# Metro_Mini_Rev_B.net
KiCad netlist of a schematic drawn in EAGLE
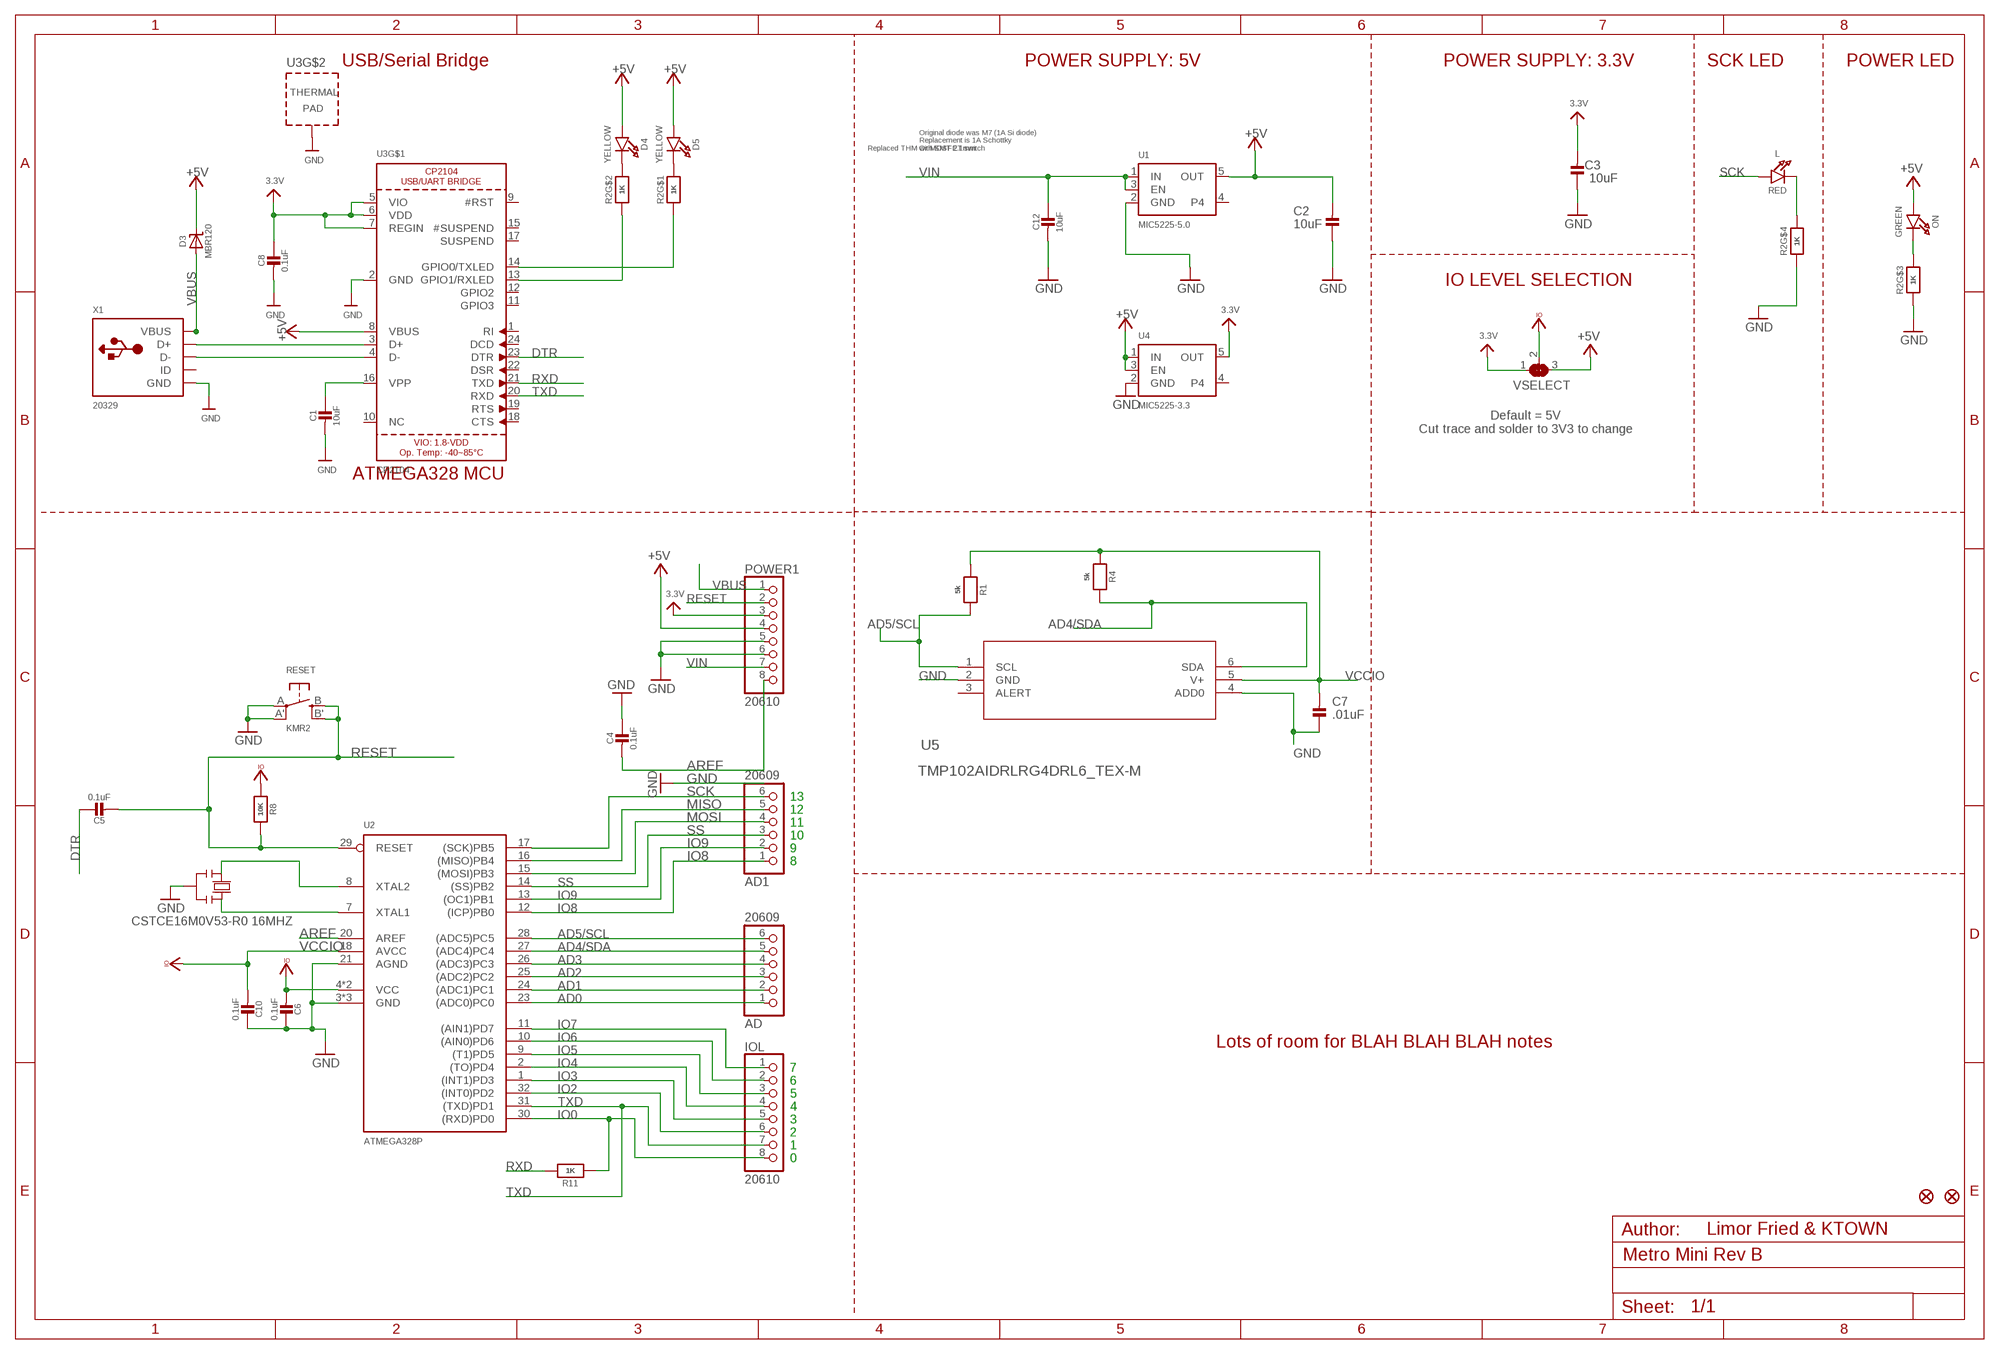
[diagram p0: schematic, sheet 1]

(export (version "E")
  (design (tool "Eeschema 10.0.6"))
  (components
    (comp (ref "AD")
      (value "20609")
      (footprint "eagle-import:1X06_ROUND")
      (libsource (lib "eagle-import") (part "HEADER-1X6ROUND"))
    )
    (comp (ref "AD1")
      (value "20609")
      (footprint "eagle-import:1X06_ROUND")
      (libsource (lib "eagle-import") (part "HEADER-1X6ROUND"))
    )
    (comp (ref "C1")
      (value "10uF")
      (footprint "eagle-import:0805-NO")
      (libsource (lib "eagle-import") (part "CAP_CERAMIC0805-NOOUTLINE"))
    )
    (comp (ref "C2")
      (value "10uF")
      (footprint "eagle-import:0805-NO")
      (libsource (lib "eagle-import") (part "CAP_CERAMIC0805-NOOUTLINE"))
    )
    (comp (ref "C3")
      (value "10uF")
      (footprint "eagle-import:0805-NO")
      (libsource (lib "eagle-import") (part "CAP_CERAMIC0805-NOOUTLINE"))
    )
    (comp (ref "C4")
      (value "0.1uF")
      (footprint "eagle-import:0805-NO")
      (libsource (lib "eagle-import") (part "CAP_CERAMIC0805-NOOUTLINE"))
    )
    (comp (ref "C5")
      (value "0.1uF")
      (footprint "eagle-import:_0805MP")
      (libsource (lib "eagle-import") (part "CAP_CERAMIC_0805MP"))
    )
    (comp (ref "C6")
      (value "0.1uF")
      (footprint "eagle-import:0805-NO")
      (libsource (lib "eagle-import") (part "CAP_CERAMIC0805-NOOUTLINE"))
    )
    (comp (ref "C7")
      (value ".01uF")
      (footprint "eagle-import:0805-NO")
      (libsource (lib "eagle-import") (part "CAP_CERAMIC0805-NOOUTLINE"))
    )
    (comp (ref "C8")
      (value "0.1uF")
      (footprint "eagle-import:0805-NO")
      (libsource (lib "eagle-import") (part "CAP_CERAMIC0805-NOOUTLINE"))
    )
    (comp (ref "C10")
      (value "0.1uF")
      (footprint "eagle-import:0805-NO")
      (libsource (lib "eagle-import") (part "CAP_CERAMIC0805-NOOUTLINE"))
    )
    (comp (ref "C12")
      (value "10uF")
      (footprint "eagle-import:0805-NO")
      (libsource (lib "eagle-import") (part "CAP_CERAMIC0805-NOOUTLINE"))
    )
    (comp (ref "D3")
      (value "MBR120")
      (footprint "eagle-import:SOD-123")
      (libsource (lib "eagle-import") (part "DIODE-SCHOTTKYSOD-123"))
    )
    (comp (ref "D4")
      (value "YELLOW")
      (footprint "eagle-import:CHIPLED_0805_NOOUTLINE")
      (libsource (lib "eagle-import") (part "LED0805_NOOUTLINE"))
    )
    (comp (ref "D5")
      (value "YELLOW")
      (footprint "eagle-import:CHIPLED_0805_NOOUTLINE")
      (libsource (lib "eagle-import") (part "LED0805_NOOUTLINE"))
    )
    (comp (ref "FD1")
      (value "FIDUCIAL\"\"")
      (footprint "eagle-import:FIDUCIAL_1MM")
      (libsource (lib "eagle-import") (part "FIDUCIAL{dblquote}{dblquote}"))
    )
    (comp (ref "FD2")
      (value "FIDUCIAL\"\"")
      (footprint "eagle-import:FIDUCIAL_1MM")
      (libsource (lib "eagle-import") (part "FIDUCIAL{dblquote}{dblquote}"))
    )
    (comp (ref "IOL")
      (value "20610")
      (footprint "eagle-import:1X08_ROUND")
      (libsource (lib "eagle-import") (part "HEADER-1X8ROUND"))
    )
    (comp (ref "L")
      (value "RED")
      (footprint "eagle-import:CHIPLED_0805_NOOUTLINE")
      (libsource (lib "eagle-import") (part "LED0805_NOOUTLINE"))
    )
    (comp (ref "ON")
      (value "GREEN")
      (footprint "eagle-import:CHIPLED_0805_NOOUTLINE")
      (libsource (lib "eagle-import") (part "LED0805_NOOUTLINE"))
    )
    (comp (ref "POWER1")
      (value "20610")
      (footprint "eagle-import:1X08_ROUND_70")
      (libsource (lib "eagle-import") (part "HEADER-1X870MIL"))
    )
    (comp (ref "R1")
      (value "5k")
      (footprint "eagle-import:0805-NO")
      (libsource (lib "eagle-import") (part "RESISTOR0805_NOOUTLINE"))
    )
    (comp (ref "R2")
      (value "1K")
      (footprint "eagle-import:RESPACK_4X0603")
      (libsource (lib "eagle-import") (part "RESISTOR_4PACK"))
    )
    (comp (ref "R4")
      (value "5k")
      (footprint "eagle-import:0805-NO")
      (libsource (lib "eagle-import") (part "RESISTOR0805_NOOUTLINE"))
    )
    (comp (ref "R8")
      (value "10K")
      (footprint "eagle-import:0805-NO")
      (libsource (lib "eagle-import") (part "RESISTOR0805_NOOUTLINE"))
    )
    (comp (ref "R11")
      (value "1K")
      (footprint "eagle-import:0805-NO")
      (libsource (lib "eagle-import") (part "RESISTOR0805_NOOUTLINE"))
    )
    (comp (ref "RESET")
      (value "KMR2")
      (footprint "eagle-import:BTN_KMR2_4.6X2.8")
      (libsource (lib "eagle-import") (part "SWITCH_TACT_SMT4.6X2.8"))
    )
    (comp (ref "U1")
      (value "MIC5225-5.0")
      (footprint "eagle-import:SOT23-5")
      (libsource (lib "eagle-import") (part "VREG_SOT23-5"))
    )
    (comp (ref "U2")
      (value "ATMEGA328P")
      (footprint "eagle-import:MLF32-TH")
      (libsource (lib "eagle-import") (part "ATMEGA328P"))
    )
    (comp (ref "U3")
      (value "CP2104")
      (footprint "eagle-import:QFN24_4MM_SMSC")
      (libsource (lib "eagle-import") (part "CP2104"))
    )
    (comp (ref "U4")
      (value "MIC5225-3.3")
      (footprint "eagle-import:SOT23-5")
      (libsource (lib "eagle-import") (part "VREG_SOT23-5"))
    )
    (comp (ref "U5")
      (value "TMP102AIDRLRG4DRL6_TEX-M")
      (footprint "eagle-import:DRL6_TEX-M")
      (fields
        (field (name "MANUFACTURER") "Texas Instruments")
        (field (name "MANUFACTURER_PART_NUMBER") "TMP102AIDRLRG4")
        (field (name "COPYRIGHT") "Copyright (C) 2018 Accelerated Designs. All rights reserved")
      )
      (libsource (lib "eagle-import") (part "TMP102AIDRLRG4DRL6_TEX-M"))
    )
    (comp (ref "VSELECT")
      (value "SOLDERJUMPER_2WAY")
      (footprint "eagle-import:SOLDERJUMPER_2WAY_OPEN_NOPASTE")
      (libsource (lib "eagle-import") (part "SOLDERJUMPER_2WAY"))
    )
    (comp (ref "X1")
      (value "20329")
      (footprint "eagle-import:4UCONN_20329_V2")
      (libsource (lib "eagle-import") (part "USB_MICRO_20329_V2"))
    )
    (comp (ref "Y2")
      (value "CSTCE16M0V53-R0 16MHZ")
      (footprint "eagle-import:RESONATOR")
      (libsource (lib "eagle-import") (part "RESONATORMU"))
    )
  )
  (nets
    (net (code "1") (name "+5V") (class "Default")
      (node (ref "C2") (pin "2") (pinfunction "2_2") (pintype "passive"))
      (node (ref "D3") (pin "C") (pinfunction "C_C") (pintype "passive"))
      (node (ref "D4") (pin "A") (pinfunction "A_A") (pintype "passive"))
      (node (ref "D5") (pin "A") (pinfunction "A_A") (pintype "passive"))
      (node (ref "ON") (pin "A") (pinfunction "A_A") (pintype "passive"))
      (node (ref "POWER1") (pin "4") (pinfunction "4_4") (pintype "passive"))
      (node (ref "U1") (pin "5") (pinfunction "OUT_5") (pintype "power_in"))
      (node (ref "U3") (pin "8") (pinfunction "VBUS_8") (pintype "power_in"))
      (node (ref "U4") (pin "1") (pinfunction "IN_1") (pintype "power_in"))
      (node (ref "U4") (pin "3") (pinfunction "EN_3") (pintype "input"))
      (node (ref "VSELECT") (pin "3") (pinfunction "3_3") (pintype "passive"))
    )
    (net (code "2") (name "/AD0") (class "Default")
      (node (ref "AD") (pin "1") (pinfunction "1_1") (pintype "passive"))
      (node (ref "U2") (pin "23") (pinfunction "(ADC0)PC0_23") (pintype "bidirectional"))
    )
    (net (code "3") (name "/AD1") (class "Default")
      (node (ref "AD") (pin "2") (pinfunction "2_2") (pintype "passive"))
      (node (ref "U2") (pin "24") (pinfunction "(ADC1)PC1_24") (pintype "bidirectional"))
    )
    (net (code "4") (name "/AD2") (class "Default")
      (node (ref "AD") (pin "3") (pinfunction "3_3") (pintype "passive"))
      (node (ref "U2") (pin "25") (pinfunction "(ADC2)PC2_25") (pintype "bidirectional"))
    )
    (net (code "5") (name "/AD3") (class "Default")
      (node (ref "AD") (pin "4") (pinfunction "4_4") (pintype "passive"))
      (node (ref "U2") (pin "26") (pinfunction "(ADC3)PC3_26") (pintype "bidirectional"))
    )
    (net (code "6") (name "/AD4{slash}SDA") (class "Default")
      (node (ref "AD") (pin "5") (pinfunction "5_5") (pintype "passive"))
      (node (ref "R4") (pin "2") (pinfunction "2_2") (pintype "passive"))
      (node (ref "U2") (pin "27") (pinfunction "(ADC4)PC4_27") (pintype "bidirectional"))
      (node (ref "U5") (pin "6") (pinfunction "SDA_6") (pintype "passive"))
    )
    (net (code "7") (name "/AD5{slash}SCL") (class "Default")
      (node (ref "AD") (pin "6") (pinfunction "6_6") (pintype "passive"))
      (node (ref "R1") (pin "2") (pinfunction "2_2") (pintype "passive"))
      (node (ref "U2") (pin "28") (pinfunction "(ADC5)PC5_28") (pintype "bidirectional"))
      (node (ref "U5") (pin "1") (pinfunction "SCL_1") (pintype "passive"))
    )
    (net (code "8") (name "/AREF") (class "Default")
      (node (ref "C4") (pin "2") (pinfunction "2_2") (pintype "passive"))
      (node (ref "POWER1") (pin "8") (pinfunction "8_8") (pintype "passive"))
      (node (ref "U2") (pin "20") (pinfunction "AREF_20") (pintype "power_in"))
    )
    (net (code "9") (name "/DTR") (class "Default")
      (node (ref "C5") (pin "1") (pinfunction "1_1") (pintype "passive"))
      (node (ref "U3") (pin "23") (pinfunction "DTR_23") (pintype "output"))
    )
    (net (code "10") (name "/IO0") (class "Default")
      (node (ref "IOL") (pin "8") (pinfunction "8_8") (pintype "passive"))
      (node (ref "R11") (pin "1") (pinfunction "1_1") (pintype "passive"))
      (node (ref "U2") (pin "30") (pinfunction "(RXD)PD0_30") (pintype "bidirectional"))
    )
    (net (code "11") (name "/IO2") (class "Default")
      (node (ref "IOL") (pin "6") (pinfunction "6_6") (pintype "passive"))
      (node (ref "U2") (pin "32") (pinfunction "(INT0)PD2_32") (pintype "bidirectional"))
    )
    (net (code "12") (name "/IO3") (class "Default")
      (node (ref "IOL") (pin "5") (pinfunction "5_5") (pintype "passive"))
      (node (ref "U2") (pin "1") (pinfunction "(INT1)PD3_1") (pintype "bidirectional"))
    )
    (net (code "13") (name "/IO4") (class "Default")
      (node (ref "IOL") (pin "4") (pinfunction "4_4") (pintype "passive"))
      (node (ref "U2") (pin "2") (pinfunction "(TO)PD4_2") (pintype "bidirectional"))
    )
    (net (code "14") (name "/IO5") (class "Default")
      (node (ref "IOL") (pin "3") (pinfunction "3_3") (pintype "passive"))
      (node (ref "U2") (pin "9") (pinfunction "(T1)PD5_9") (pintype "bidirectional"))
    )
    (net (code "15") (name "/IO6") (class "Default")
      (node (ref "IOL") (pin "2") (pinfunction "2_2") (pintype "passive"))
      (node (ref "U2") (pin "10") (pinfunction "(AIN0)PD6_10") (pintype "bidirectional"))
    )
    (net (code "16") (name "/IO7") (class "Default")
      (node (ref "IOL") (pin "1") (pinfunction "1_1") (pintype "passive"))
      (node (ref "U2") (pin "11") (pinfunction "(AIN1)PD7_11") (pintype "bidirectional"))
    )
    (net (code "17") (name "/IO8") (class "Default")
      (node (ref "AD1") (pin "1") (pinfunction "1_1") (pintype "passive"))
      (node (ref "U2") (pin "12") (pinfunction "(ICP)PB0_12") (pintype "bidirectional"))
    )
    (net (code "18") (name "/IO9") (class "Default")
      (node (ref "AD1") (pin "2") (pinfunction "2_2") (pintype "passive"))
      (node (ref "U2") (pin "13") (pinfunction "(OC1)PB1_13") (pintype "bidirectional"))
    )
    (net (code "19") (name "/MISO") (class "Default")
      (node (ref "AD1") (pin "5") (pinfunction "5_5") (pintype "passive"))
      (node (ref "U2") (pin "16") (pinfunction "(MISO)PB4_16") (pintype "bidirectional"))
    )
    (net (code "20") (name "/MOSI") (class "Default")
      (node (ref "AD1") (pin "4") (pinfunction "4_4") (pintype "passive"))
      (node (ref "U2") (pin "15") (pinfunction "(MOSI)PB3_15") (pintype "bidirectional"))
    )
    (net (code "21") (name "/RESET") (class "Default")
      (node (ref "C5") (pin "2") (pinfunction "2_2") (pintype "passive"))
      (node (ref "POWER1") (pin "2") (pinfunction "2_2") (pintype "passive"))
      (node (ref "R8") (pin "1") (pinfunction "1_1") (pintype "passive"))
      (node (ref "RESET") (pin "B") (pinfunction "S_B") (pintype "passive"))
      (node (ref "RESET") (pin "B'") (pinfunction "S1_B'") (pintype "passive"))
      (node (ref "U2") (pin "29") (pinfunction "RESET_29") (pintype "bidirectional"))
    )
    (net (code "22") (name "/RXD") (class "Default")
      (node (ref "R11") (pin "2") (pinfunction "2_2") (pintype "passive"))
      (node (ref "U3") (pin "21") (pinfunction "TXD_21") (pintype "output"))
    )
    (net (code "23") (name "/SCK") (class "Default")
      (node (ref "AD1") (pin "6") (pinfunction "6_6") (pintype "passive"))
      (node (ref "L") (pin "A") (pinfunction "A_A") (pintype "passive"))
      (node (ref "U2") (pin "17") (pinfunction "(SCK)PB5_17") (pintype "bidirectional"))
    )
    (net (code "24") (name "/SS") (class "Default")
      (node (ref "AD1") (pin "3") (pinfunction "3_3") (pintype "passive"))
      (node (ref "U2") (pin "14") (pinfunction "(SS)PB2_14") (pintype "bidirectional"))
    )
    (net (code "25") (name "/TXD") (class "Default")
      (node (ref "IOL") (pin "7") (pinfunction "7_7") (pintype "passive"))
      (node (ref "U2") (pin "31") (pinfunction "(TXD)PD1_31") (pintype "bidirectional"))
      (node (ref "U3") (pin "20") (pinfunction "RXD_20") (pintype "input"))
    )
    (net (code "26") (name "/VBUS") (class "Default")
      (node (ref "D3") (pin "A") (pinfunction "A_A") (pintype "passive"))
      (node (ref "POWER1") (pin "1") (pinfunction "1_1") (pintype "passive"))
      (node (ref "X1") (pin "VBUS") (pinfunction "VBUS_VBUS") (pintype "power_in"))
    )
    (net (code "27") (name "/VIN") (class "Default")
      (node (ref "C12") (pin "1") (pinfunction "1_1") (pintype "passive"))
      (node (ref "POWER1") (pin "7") (pinfunction "7_7") (pintype "passive"))
      (node (ref "U1") (pin "1") (pinfunction "IN_1") (pintype "power_in"))
      (node (ref "U1") (pin "3") (pinfunction "EN_3") (pintype "input"))
    )
    (net (code "28") (name "3.3V") (class "Default")
      (node (ref "C3") (pin "2") (pinfunction "2_2") (pintype "passive"))
      (node (ref "C8") (pin "1") (pinfunction "1_1") (pintype "passive"))
      (node (ref "POWER1") (pin "3") (pinfunction "3_3") (pintype "passive"))
      (node (ref "U3") (pin "5") (pinfunction "VIO_5") (pintype "power_in"))
      (node (ref "U3") (pin "6") (pinfunction "VDD_6") (pintype "power_in"))
      (node (ref "U3") (pin "7") (pinfunction "REGIN_7") (pintype "power_in"))
      (node (ref "U4") (pin "5") (pinfunction "OUT_5") (pintype "power_in"))
      (node (ref "VSELECT") (pin "1") (pinfunction "1_1") (pintype "passive"))
    )
    (net (code "29") (name "GND") (class "Default")
      (node (ref "C1") (pin "2") (pinfunction "2_2") (pintype "passive"))
      (node (ref "C10") (pin "1") (pinfunction "1_1") (pintype "passive"))
      (node (ref "C12") (pin "2") (pinfunction "2_2") (pintype "passive"))
      (node (ref "C2") (pin "1") (pinfunction "1_1") (pintype "passive"))
      (node (ref "C3") (pin "1") (pinfunction "1_1") (pintype "passive"))
      (node (ref "C4") (pin "1") (pinfunction "1_1") (pintype "passive"))
      (node (ref "C6") (pin "1") (pinfunction "1_1") (pintype "passive"))
      (node (ref "C7") (pin "1") (pinfunction "1_1") (pintype "passive"))
      (node (ref "C8") (pin "2") (pinfunction "2_2") (pintype "passive"))
      (node (ref "POWER1") (pin "5") (pinfunction "5_5") (pintype "passive"))
      (node (ref "POWER1") (pin "6") (pinfunction "6_6") (pintype "passive"))
      (node (ref "R2") (pin "3") (pinfunction "1_3") (pintype "passive"))
      (node (ref "R2") (pin "4") (pinfunction "1_4") (pintype "passive"))
      (node (ref "RESET") (pin "A") (pinfunction "P_A") (pintype "passive"))
      (node (ref "RESET") (pin "A'") (pinfunction "P1_A'") (pintype "passive"))
      (node (ref "U1") (pin "2") (pinfunction "GND_2") (pintype "power_in"))
      (node (ref "U2") (pin "21") (pinfunction "AGND_21") (pintype "power_in"))
      (node (ref "U2") (pin "3") (pinfunction "GND_3") (pintype "power_in"))
      (node (ref "U2") (pin "5") (pinfunction "GND_5") (pintype "power_in"))
      (node (ref "U2") (pin "TH") (pinfunction "GND_TH") (pintype "power_in"))
      (node (ref "U3") (pin "2") (pinfunction "GND_2") (pintype "power_in"))
      (node (ref "U3") (pin "THERM") (pinfunction "TP_THERM") (pintype "power_in"))
      (node (ref "U4") (pin "2") (pinfunction "GND_2") (pintype "power_in"))
      (node (ref "U5") (pin "2") (pinfunction "GND_2") (pintype "power_in"))
      (node (ref "U5") (pin "4") (pinfunction "ADD0_4") (pintype "passive"))
      (node (ref "X1") (pin "BASE@1") (pinfunction "GND_BASE@1") (pintype "power_in"))
      (node (ref "X1") (pin "BASE@2") (pinfunction "GND_BASE@2") (pintype "power_in"))
      (node (ref "X1") (pin "GND") (pinfunction "GND_GND") (pintype "power_in"))
      (node (ref "X1") (pin "SPRT@1") (pinfunction "GND_SPRT@1") (pintype "power_in"))
      (node (ref "X1") (pin "SPRT@2") (pinfunction "GND_SPRT@2") (pintype "power_in"))
      (node (ref "X1") (pin "SPRT@3") (pinfunction "GND_SPRT@3") (pintype "power_in"))
      (node (ref "X1") (pin "SPRT@4") (pinfunction "GND_SPRT@4") (pintype "power_in"))
      (node (ref "Y2") (pin "2") (pinfunction "2_2") (pintype "passive"))
    )
    (net (code "30") (name "Net-(R2A-2)") (class "Default")
      (node (ref "D5") (pin "C") (pinfunction "C_C") (pintype "passive"))
      (node (ref "R2") (pin "8") (pinfunction "2_8") (pintype "passive"))
    )
    (net (code "31") (name "Net-(R2B-1)") (class "Default")
      (node (ref "R2") (pin "2") (pinfunction "1_2") (pintype "passive"))
      (node (ref "U3") (pin "13") (pinfunction "GPIO1/RXLED_13") (pintype "bidirectional"))
    )
    (net (code "32") (name "Net-(R2B-2)") (class "Default")
      (node (ref "D4") (pin "C") (pinfunction "C_C") (pintype "passive"))
      (node (ref "R2") (pin "7") (pinfunction "2_7") (pintype "passive"))
    )
    (net (code "33") (name "Net-(R2C-2)") (class "Default")
      (node (ref "ON") (pin "C") (pinfunction "C_C") (pintype "passive"))
      (node (ref "R2") (pin "6") (pinfunction "2_6") (pintype "passive"))
    )
    (net (code "34") (name "Net-(R2D-2)") (class "Default")
      (node (ref "L") (pin "C") (pinfunction "C_C") (pintype "passive"))
      (node (ref "R2") (pin "5") (pinfunction "2_5") (pintype "passive"))
    )
    (net (code "35") (name "Net-(U2-XTAL1)") (class "Default")
      (node (ref "U2") (pin "7") (pinfunction "XTAL1_7") (pintype "bidirectional"))
      (node (ref "Y2") (pin "3") (pinfunction "3_3") (pintype "passive"))
    )
    (net (code "36") (name "Net-(U2-XTAL2)") (class "Default")
      (node (ref "U2") (pin "8") (pinfunction "XTAL2_8") (pintype "bidirectional"))
      (node (ref "Y2") (pin "1") (pinfunction "1_1") (pintype "passive"))
    )
    (net (code "37") (name "Net-(U3A-D+)") (class "Default")
      (node (ref "U3") (pin "3") (pinfunction "D+_3") (pintype "bidirectional"))
      (node (ref "X1") (pin "D+") (pinfunction "D+_D+") (pintype "bidirectional"))
    )
    (net (code "38") (name "Net-(U3A-D-)") (class "Default")
      (node (ref "U3") (pin "4") (pinfunction "D-_4") (pintype "bidirectional"))
      (node (ref "X1") (pin "D-") (pinfunction "D-_D-") (pintype "bidirectional"))
    )
    (net (code "39") (name "Net-(U3A-GPIO0{slash}TXLED)") (class "Default")
      (node (ref "R2") (pin "1") (pinfunction "1_1") (pintype "passive"))
      (node (ref "U3") (pin "14") (pinfunction "GPIO0/TXLED_14") (pintype "bidirectional"))
    )
    (net (code "40") (name "Net-(U3A-VPP)") (class "Default")
      (node (ref "C1") (pin "1") (pinfunction "1_1") (pintype "passive"))
      (node (ref "U3") (pin "16") (pinfunction "VPP_16") (pintype "bidirectional"))
    )
    (net (code "41") (name "VCCIO") (class "Default")
      (node (ref "C10") (pin "2") (pinfunction "2_2") (pintype "passive"))
      (node (ref "C6") (pin "2") (pinfunction "2_2") (pintype "passive"))
      (node (ref "C7") (pin "2") (pinfunction "2_2") (pintype "passive"))
      (node (ref "R1") (pin "1") (pinfunction "1_1") (pintype "passive"))
      (node (ref "R4") (pin "1") (pinfunction "1_1") (pintype "passive"))
      (node (ref "R8") (pin "2") (pinfunction "2_2") (pintype "passive"))
      (node (ref "U2") (pin "18") (pinfunction "AVCC_18") (pintype "power_in"))
      (node (ref "U2") (pin "4") (pinfunction "VCC_4") (pintype "power_in"))
      (node (ref "U2") (pin "6") (pinfunction "VCC_6") (pintype "power_in"))
      (node (ref "U5") (pin "5") (pinfunction "V+_5") (pintype "power_in"))
      (node (ref "VSELECT") (pin "2") (pinfunction "2_2") (pintype "passive"))
    )
    (net (code "42") (name "unconnected-(U1-P4-Pad4)") (class "Default")
      (node (ref "U1") (pin "4") (pinfunction "P4_4") (pintype "bidirectional"))
    )
    (net (code "43") (name "unconnected-(U3A-#RST-Pad9)") (class "Default")
      (node (ref "U3") (pin "9") (pinfunction "#RST_9") (pintype "bidirectional"))
    )
    (net (code "44") (name "unconnected-(U3A-#SUSPEND-Pad15)") (class "Default")
      (node (ref "U3") (pin "15") (pinfunction "#SUSPEND_15") (pintype "output"))
    )
    (net (code "45") (name "unconnected-(U3A-CTS-Pad18)") (class "Default")
      (node (ref "U3") (pin "18") (pinfunction "CTS_18") (pintype "input"))
    )
    (net (code "46") (name "unconnected-(U3A-DCD-Pad24)") (class "Default")
      (node (ref "U3") (pin "24") (pinfunction "DCD_24") (pintype "input"))
    )
    (net (code "47") (name "unconnected-(U3A-DSR-Pad22)") (class "Default")
      (node (ref "U3") (pin "22") (pinfunction "DSR_22") (pintype "input"))
    )
    (net (code "48") (name "unconnected-(U3A-GPIO2-Pad12)") (class "Default")
      (node (ref "U3") (pin "12") (pinfunction "GPIO2_12") (pintype "bidirectional"))
    )
    (net (code "49") (name "unconnected-(U3A-GPIO3-Pad11)") (class "Default")
      (node (ref "U3") (pin "11") (pinfunction "GPIO3_11") (pintype "bidirectional"))
    )
    (net (code "50") (name "unconnected-(U3A-NC-Pad10)") (class "Default")
      (node (ref "U3") (pin "10") (pinfunction "NC_10") (pintype "no_connect"))
    )
    (net (code "51") (name "unconnected-(U3A-RI-Pad1)") (class "Default")
      (node (ref "U3") (pin "1") (pinfunction "RI_1") (pintype "input"))
    )
    (net (code "52") (name "unconnected-(U3A-RTS-Pad19)") (class "Default")
      (node (ref "U3") (pin "19") (pinfunction "RTS_19") (pintype "output"))
    )
    (net (code "53") (name "unconnected-(U3A-SUSPEND-Pad17)") (class "Default")
      (node (ref "U3") (pin "17") (pinfunction "SUSPEND_17") (pintype "output"))
    )
    (net (code "54") (name "unconnected-(U4-P4-Pad4)") (class "Default")
      (node (ref "U4") (pin "4") (pinfunction "P4_4") (pintype "bidirectional"))
    )
    (net (code "55") (name "unconnected-(U5-ALERT-Pad3)") (class "Default")
      (node (ref "U5") (pin "3") (pinfunction "ALERT_3") (pintype "passive"))
    )
    (net (code "56") (name "unconnected-(X1-PadID)") (class "Default")
      (node (ref "X1") (pin "ID") (pinfunction "ID_ID") (pintype "bidirectional"))
    )
  )
)
